# B117X.net
KiCad netlist of a schematic drawn in EAGLE
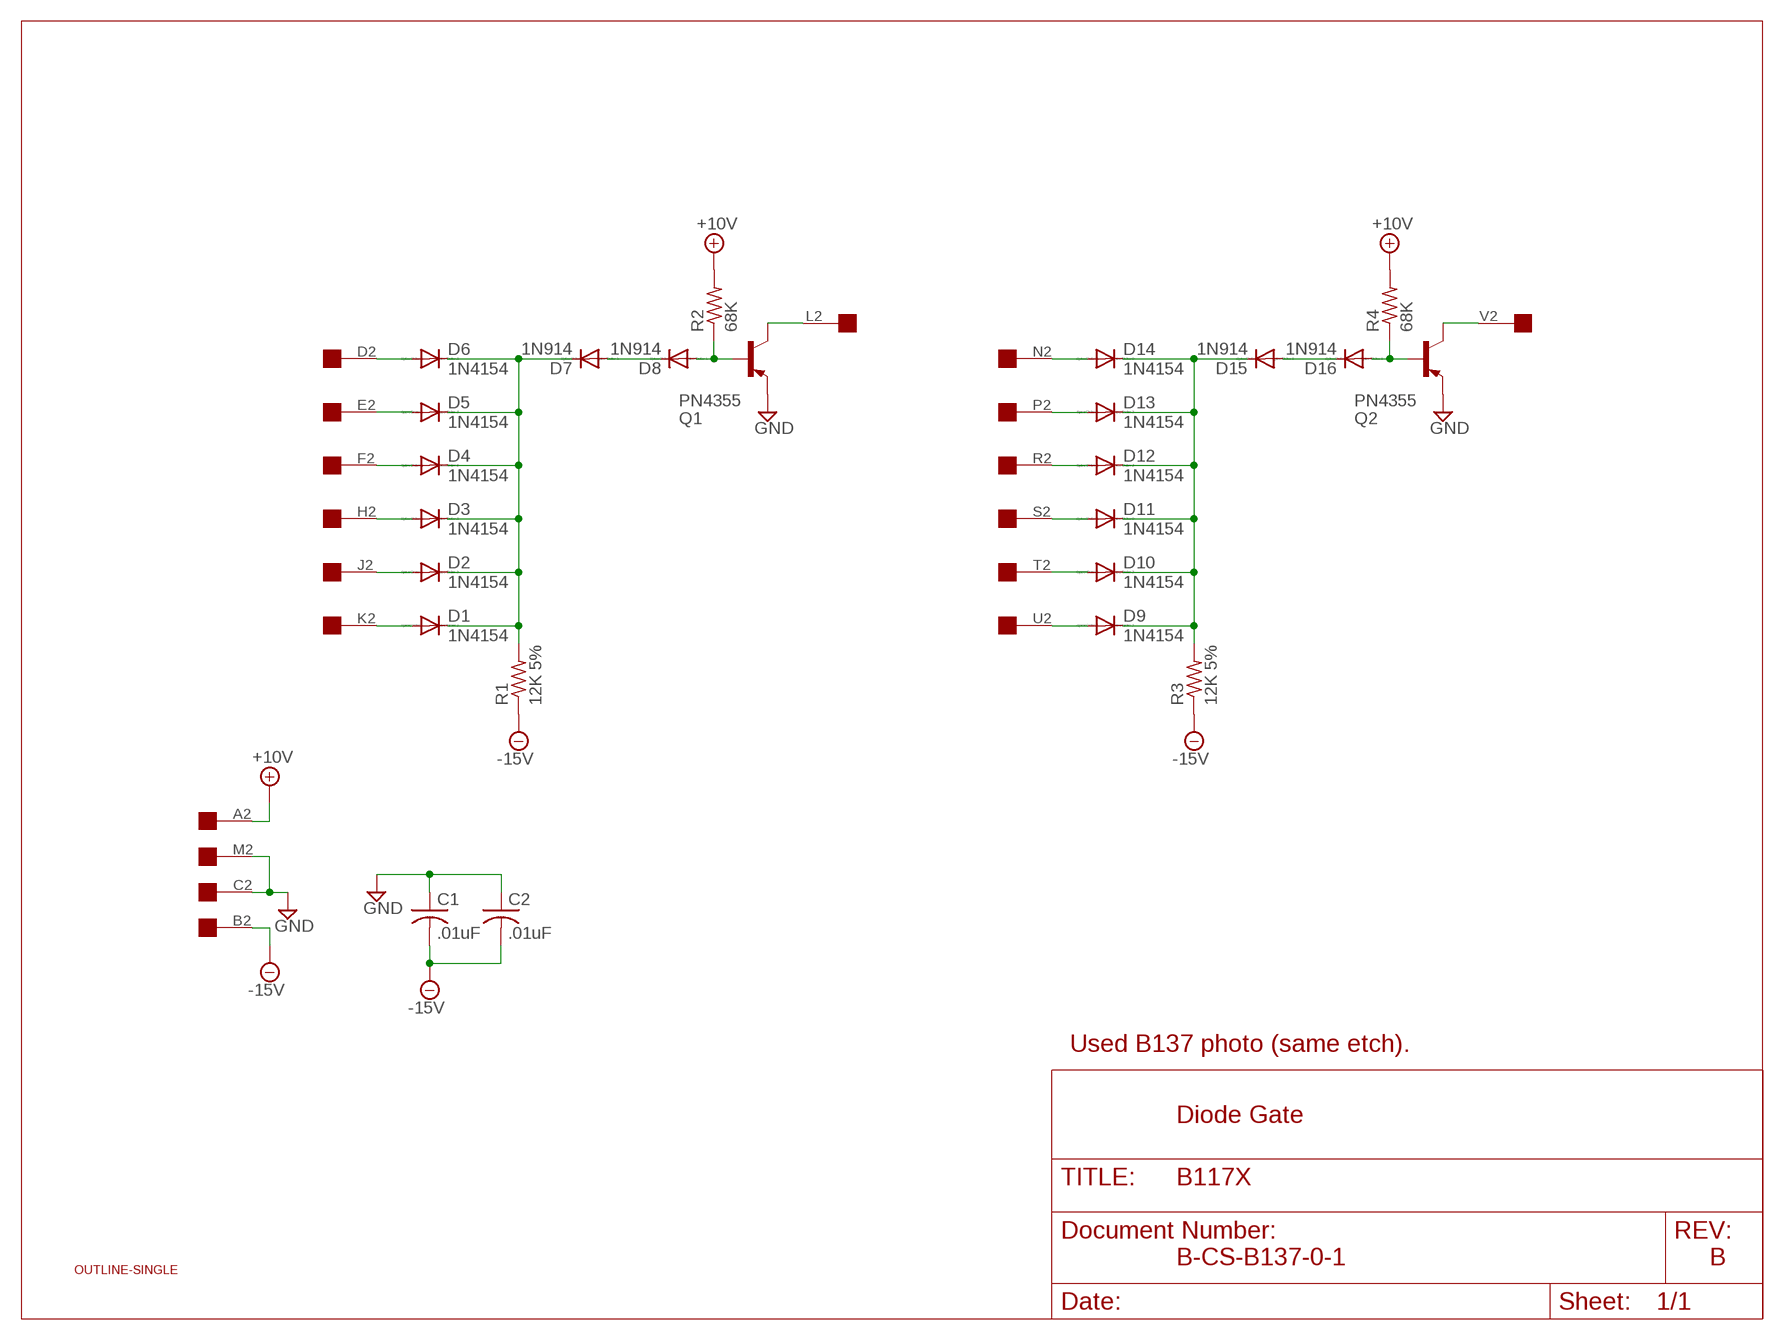
[diagram p0: schematic, sheet 1]

(export (version "E")
  (design (tool "Eeschema 10.0.6"))
  (components
    (comp (ref "C1")
      (value ".01uF")
      (footprint "eagle-import:C050-025X075")
      (libsource (lib "eagle-import") (part "C-US050-025X075"))
    )
    (comp (ref "C2")
      (value ".01uF")
      (footprint "eagle-import:C050-025X075")
      (libsource (lib "eagle-import") (part "C-US050-025X075"))
    )
    (comp (ref "D1")
      (value "1N4154")
      (footprint "eagle-import:DO35-10")
      (libsource (lib "eagle-import") (part "DIODE-DO35-10"))
    )
    (comp (ref "D2")
      (value "1N4154")
      (footprint "eagle-import:DO35-10")
      (libsource (lib "eagle-import") (part "DIODE-DO35-10"))
    )
    (comp (ref "D3")
      (value "1N4154")
      (footprint "eagle-import:DO35-10")
      (libsource (lib "eagle-import") (part "DIODE-DO35-10"))
    )
    (comp (ref "D4")
      (value "1N4154")
      (footprint "eagle-import:DO35-10")
      (libsource (lib "eagle-import") (part "DIODE-DO35-10"))
    )
    (comp (ref "D5")
      (value "1N4154")
      (footprint "eagle-import:DO35-10")
      (libsource (lib "eagle-import") (part "DIODE-DO35-10"))
    )
    (comp (ref "D6")
      (value "1N4154")
      (footprint "eagle-import:DO35-10")
      (libsource (lib "eagle-import") (part "DIODE-DO35-10"))
    )
    (comp (ref "D7")
      (value "1N914")
      (footprint "eagle-import:DO35-10")
      (libsource (lib "eagle-import") (part "DIODE-DO35-10"))
    )
    (comp (ref "D8")
      (value "1N914")
      (footprint "eagle-import:DO35-10")
      (libsource (lib "eagle-import") (part "DIODE-DO35-10"))
    )
    (comp (ref "D9")
      (value "1N4154")
      (footprint "eagle-import:DO35-10")
      (libsource (lib "eagle-import") (part "DIODE-DO35-10"))
    )
    (comp (ref "D10")
      (value "1N4154")
      (footprint "eagle-import:DO35-10")
      (libsource (lib "eagle-import") (part "DIODE-DO35-10"))
    )
    (comp (ref "D11")
      (value "1N4154")
      (footprint "eagle-import:DO35-10")
      (libsource (lib "eagle-import") (part "DIODE-DO35-10"))
    )
    (comp (ref "D12")
      (value "1N4154")
      (footprint "eagle-import:DO35-10")
      (libsource (lib "eagle-import") (part "DIODE-DO35-10"))
    )
    (comp (ref "D13")
      (value "1N4154")
      (footprint "eagle-import:DO35-10")
      (libsource (lib "eagle-import") (part "DIODE-DO35-10"))
    )
    (comp (ref "D14")
      (value "1N4154")
      (footprint "eagle-import:DO35-10")
      (libsource (lib "eagle-import") (part "DIODE-DO35-10"))
    )
    (comp (ref "D15")
      (value "1N914")
      (footprint "eagle-import:DO35-10")
      (libsource (lib "eagle-import") (part "DIODE-DO35-10"))
    )
    (comp (ref "D16")
      (value "1N914")
      (footprint "eagle-import:DO35-10")
      (libsource (lib "eagle-import") (part "DIODE-DO35-10"))
    )
    (comp (ref "Q1")
      (value "PN4355")
      (footprint "eagle-import:TO5")
      (libsource (lib "eagle-import") (part "-PNP-TO5"))
    )
    (comp (ref "Q2")
      (value "PN4355")
      (footprint "eagle-import:TO5")
      (libsource (lib "eagle-import") (part "-PNP-TO5"))
    )
    (comp (ref "R1")
      (value "12K 5%")
      (footprint "eagle-import:0207_10")
      (libsource (lib "eagle-import") (part "R-US_0207/10"))
    )
    (comp (ref "R2")
      (value "68K")
      (footprint "eagle-import:0207_10")
      (libsource (lib "eagle-import") (part "R-US_0207/10"))
    )
    (comp (ref "R3")
      (value "12K 5%")
      (footprint "eagle-import:0207_10")
      (libsource (lib "eagle-import") (part "R-US_0207/10"))
    )
    (comp (ref "R4")
      (value "68K")
      (footprint "eagle-import:0207_10")
      (libsource (lib "eagle-import") (part "R-US_0207/10"))
    )
    (comp (ref "U$1")
      (value "OUTLINE-SINGLE")
      (footprint "eagle-import:SINGLE")
      (libsource (lib "eagle-import") (part "OUTLINE-SINGLE"))
    )
    (comp (ref "U$2")
      (value "EDGE-1")
      (footprint "eagle-import:EDGE-CON1")
      (libsource (lib "eagle-import") (part "EDGE-1"))
    )
  )
  (nets
    (net (code "1") (name "+10V") (class "Default")
      (node (ref "R2") (pin "2") (pinfunction "2_2") (pintype "passive"))
      (node (ref "R4") (pin "2") (pinfunction "2_2") (pintype "passive"))
      (node (ref "U$2") (pin "A2") (pinfunction "1_A2") (pintype "bidirectional"))
    )
    (net (code "2") (name "-15V") (class "Default")
      (node (ref "C1") (pin "2") (pinfunction "2_2") (pintype "passive"))
      (node (ref "C2") (pin "2") (pinfunction "2_2") (pintype "passive"))
      (node (ref "R1") (pin "1") (pinfunction "1_1") (pintype "passive"))
      (node (ref "R3") (pin "1") (pinfunction "1_1") (pintype "passive"))
      (node (ref "U$2") (pin "B2") (pinfunction "1_B2") (pintype "bidirectional"))
    )
    (net (code "3") (name "GND") (class "Default")
      (node (ref "C1") (pin "1") (pinfunction "1_1") (pintype "passive"))
      (node (ref "C2") (pin "1") (pinfunction "1_1") (pintype "passive"))
      (node (ref "Q1") (pin "1") (pinfunction "E_1") (pintype "passive"))
      (node (ref "Q2") (pin "1") (pinfunction "E_1") (pintype "passive"))
      (node (ref "U$2") (pin "C2") (pinfunction "1_C2") (pintype "bidirectional"))
      (node (ref "U$2") (pin "M2") (pinfunction "1_M2") (pintype "bidirectional"))
    )
    (net (code "4") (name "Net-(D1-PadC)") (class "Default")
      (node (ref "D1") (pin "C") (pinfunction "C_C") (pintype "passive"))
      (node (ref "D2") (pin "C") (pinfunction "C_C") (pintype "passive"))
      (node (ref "D3") (pin "C") (pinfunction "C_C") (pintype "passive"))
      (node (ref "D4") (pin "C") (pinfunction "C_C") (pintype "passive"))
      (node (ref "D5") (pin "C") (pinfunction "C_C") (pintype "passive"))
      (node (ref "D6") (pin "C") (pinfunction "C_C") (pintype "passive"))
      (node (ref "D7") (pin "C") (pinfunction "C_C") (pintype "passive"))
      (node (ref "R1") (pin "2") (pinfunction "2_2") (pintype "passive"))
    )
    (net (code "5") (name "Net-(D7-PadA)") (class "Default")
      (node (ref "D7") (pin "A") (pinfunction "A_A") (pintype "passive"))
      (node (ref "D8") (pin "C") (pinfunction "C_C") (pintype "passive"))
    )
    (net (code "6") (name "Net-(D10-PadC)") (class "Default")
      (node (ref "D10") (pin "C") (pinfunction "C_C") (pintype "passive"))
      (node (ref "D11") (pin "C") (pinfunction "C_C") (pintype "passive"))
      (node (ref "D12") (pin "C") (pinfunction "C_C") (pintype "passive"))
      (node (ref "D13") (pin "C") (pinfunction "C_C") (pintype "passive"))
      (node (ref "D14") (pin "C") (pinfunction "C_C") (pintype "passive"))
      (node (ref "D15") (pin "C") (pinfunction "C_C") (pintype "passive"))
      (node (ref "D9") (pin "C") (pinfunction "C_C") (pintype "passive"))
      (node (ref "R3") (pin "2") (pinfunction "2_2") (pintype "passive"))
    )
    (net (code "7") (name "Net-(D15-PadA)") (class "Default")
      (node (ref "D15") (pin "A") (pinfunction "A_A") (pintype "passive"))
      (node (ref "D16") (pin "C") (pinfunction "C_C") (pintype "passive"))
    )
    (net (code "8") (name "Net-(Q1-B)") (class "Default")
      (node (ref "D8") (pin "A") (pinfunction "A_A") (pintype "passive"))
      (node (ref "Q1") (pin "2") (pinfunction "B_2") (pintype "passive"))
      (node (ref "R2") (pin "1") (pinfunction "1_1") (pintype "passive"))
    )
    (net (code "9") (name "Net-(Q1-C)") (class "Default")
      (node (ref "Q1") (pin "3") (pinfunction "C_3") (pintype "passive"))
      (node (ref "U$2") (pin "L2") (pinfunction "1_L2") (pintype "bidirectional"))
    )
    (net (code "10") (name "Net-(Q2-B)") (class "Default")
      (node (ref "D16") (pin "A") (pinfunction "A_A") (pintype "passive"))
      (node (ref "Q2") (pin "2") (pinfunction "B_2") (pintype "passive"))
      (node (ref "R4") (pin "1") (pinfunction "1_1") (pintype "passive"))
    )
    (net (code "11") (name "Net-(Q2-C)") (class "Default")
      (node (ref "Q2") (pin "3") (pinfunction "C_3") (pintype "passive"))
      (node (ref "U$2") (pin "V2") (pinfunction "1_V2") (pintype "bidirectional"))
    )
    (net (code "12") (name "Net-(U$2D-1)") (class "Default")
      (node (ref "D6") (pin "A") (pinfunction "A_A") (pintype "passive"))
      (node (ref "U$2") (pin "D2") (pinfunction "1_D2") (pintype "bidirectional"))
    )
    (net (code "13") (name "Net-(U$2E-1)") (class "Default")
      (node (ref "D5") (pin "A") (pinfunction "A_A") (pintype "passive"))
      (node (ref "U$2") (pin "E2") (pinfunction "1_E2") (pintype "bidirectional"))
    )
    (net (code "14") (name "Net-(U$2F-1)") (class "Default")
      (node (ref "D4") (pin "A") (pinfunction "A_A") (pintype "passive"))
      (node (ref "U$2") (pin "F2") (pinfunction "1_F2") (pintype "bidirectional"))
    )
    (net (code "15") (name "Net-(U$2G-1)") (class "Default")
      (node (ref "D3") (pin "A") (pinfunction "A_A") (pintype "passive"))
      (node (ref "U$2") (pin "H2") (pinfunction "1_H2") (pintype "bidirectional"))
    )
    (net (code "16") (name "Net-(U$2H-1)") (class "Default")
      (node (ref "D2") (pin "A") (pinfunction "A_A") (pintype "passive"))
      (node (ref "U$2") (pin "J2") (pinfunction "1_J2") (pintype "bidirectional"))
    )
    (net (code "17") (name "Net-(U$2I-1)") (class "Default")
      (node (ref "D1") (pin "A") (pinfunction "A_A") (pintype "passive"))
      (node (ref "U$2") (pin "K2") (pinfunction "1_K2") (pintype "bidirectional"))
    )
    (net (code "18") (name "Net-(U$2L-1)") (class "Default")
      (node (ref "D14") (pin "A") (pinfunction "A_A") (pintype "passive"))
      (node (ref "U$2") (pin "N2") (pinfunction "1_N2") (pintype "bidirectional"))
    )
    (net (code "19") (name "Net-(U$2M-1)") (class "Default")
      (node (ref "D13") (pin "A") (pinfunction "A_A") (pintype "passive"))
      (node (ref "U$2") (pin "P2") (pinfunction "1_P2") (pintype "bidirectional"))
    )
    (net (code "20") (name "Net-(U$2N-1)") (class "Default")
      (node (ref "D12") (pin "A") (pinfunction "A_A") (pintype "passive"))
      (node (ref "U$2") (pin "R2") (pinfunction "1_R2") (pintype "bidirectional"))
    )
    (net (code "21") (name "Net-(U$2O-1)") (class "Default")
      (node (ref "D11") (pin "A") (pinfunction "A_A") (pintype "passive"))
      (node (ref "U$2") (pin "S2") (pinfunction "1_S2") (pintype "bidirectional"))
    )
    (net (code "22") (name "Net-(U$2P-1)") (class "Default")
      (node (ref "D10") (pin "A") (pinfunction "A_A") (pintype "passive"))
      (node (ref "U$2") (pin "T2") (pinfunction "1_T2") (pintype "bidirectional"))
    )
    (net (code "23") (name "Net-(U$2Q-1)") (class "Default")
      (node (ref "D9") (pin "A") (pinfunction "A_A") (pintype "passive"))
      (node (ref "U$2") (pin "U2") (pinfunction "1_U2") (pintype "bidirectional"))
    )
  )
)
